# pinheader_pigoda_v2.net
KiCad netlist of a schematic drawn in EAGLE
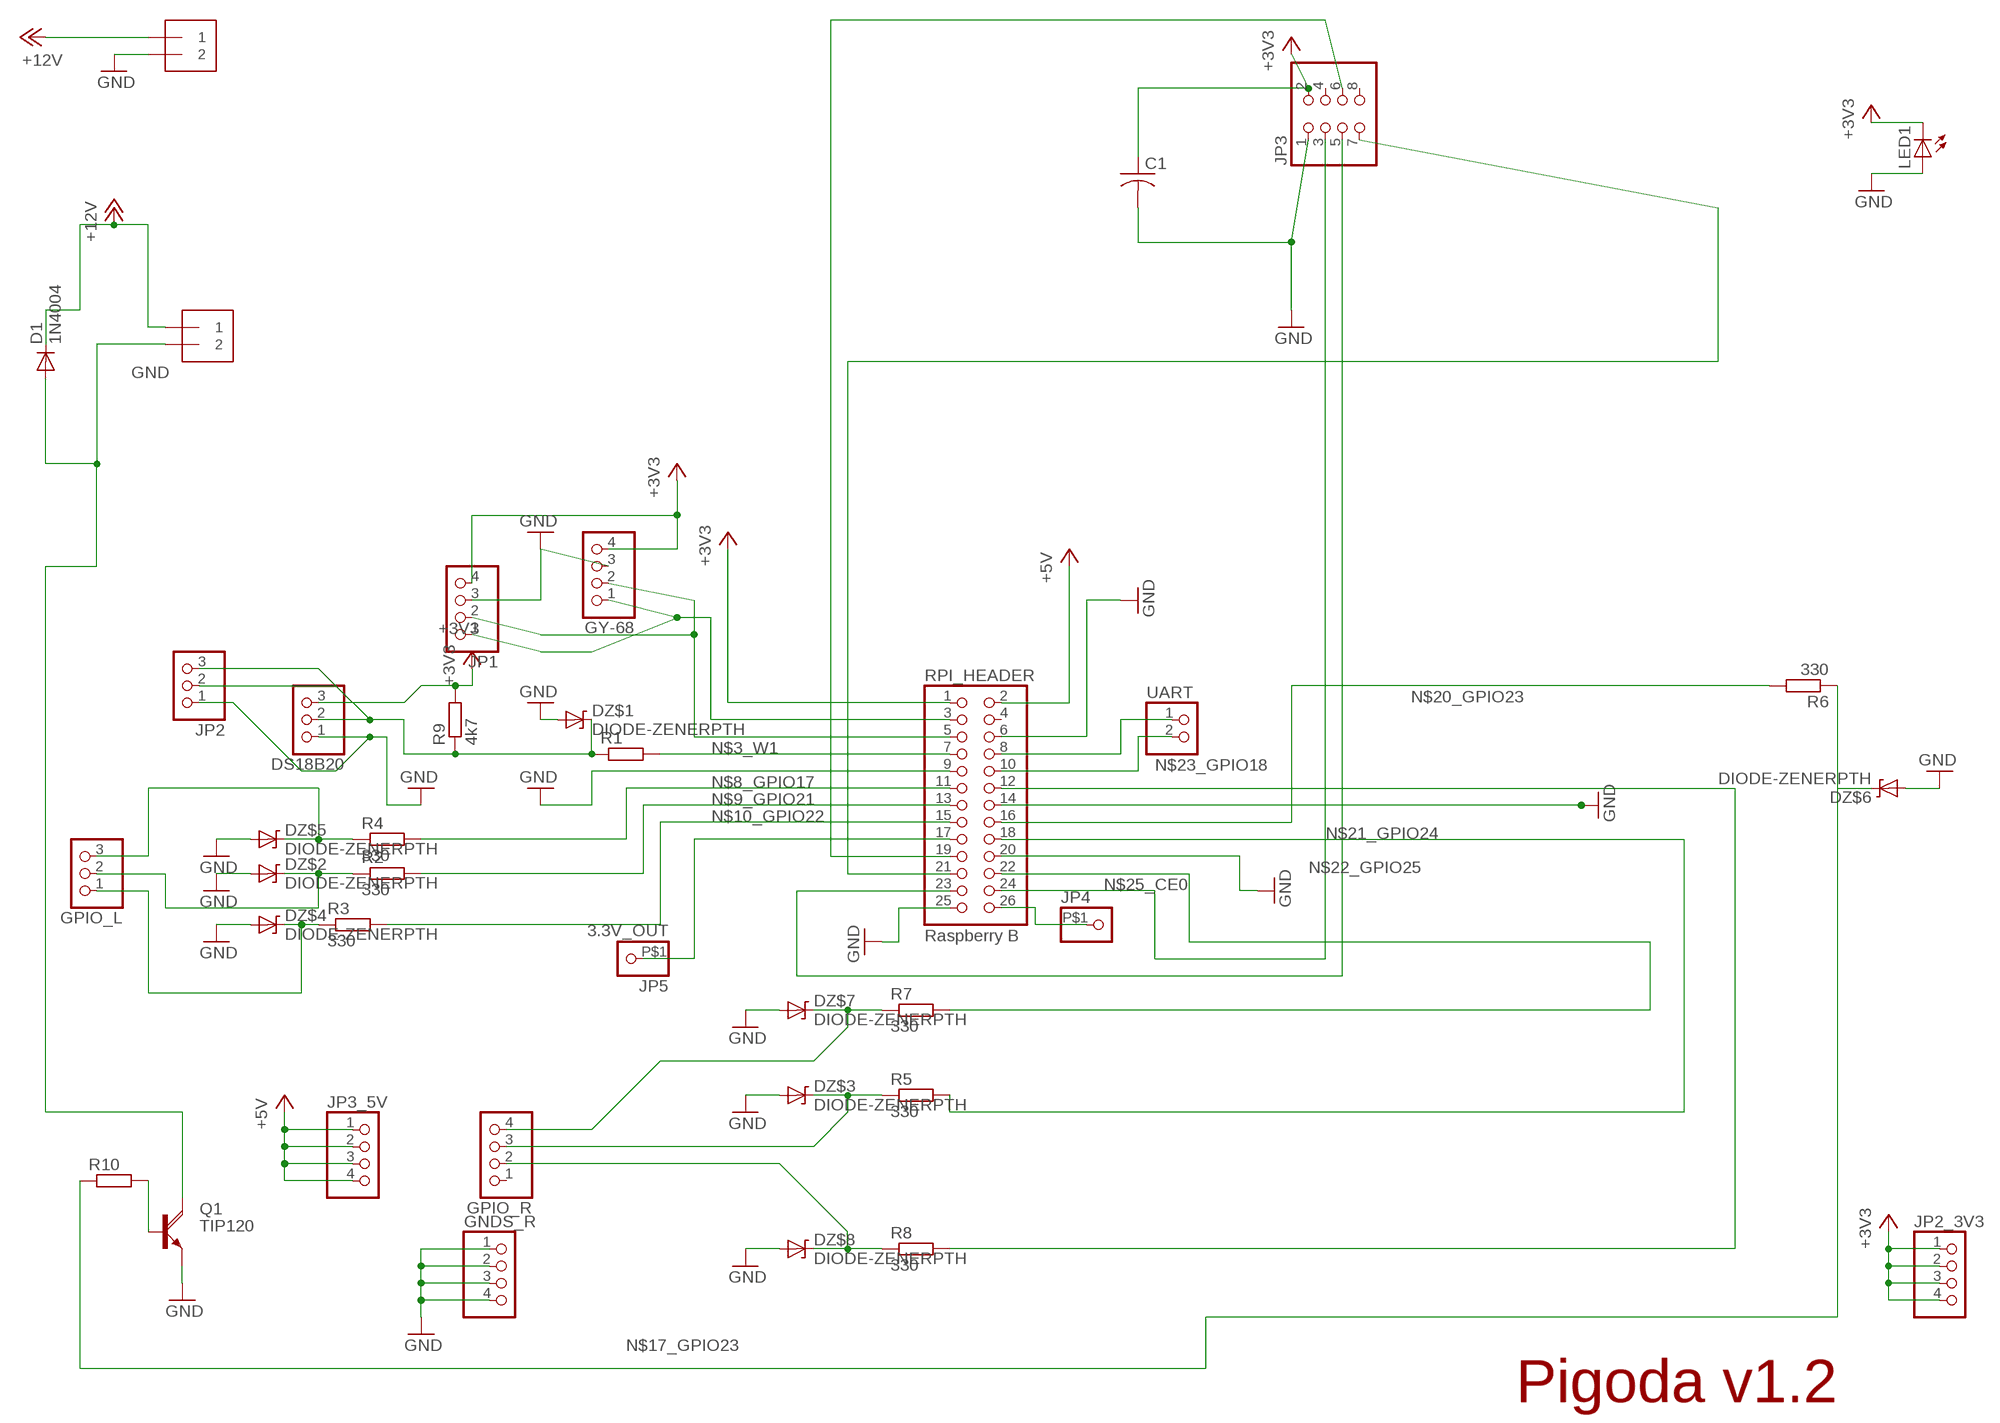
[diagram p0: schematic, sheet 1]

(export (version "E")
  (design (tool "Eeschema 10.0.6"))
  (components
    (comp (ref "C1")
      (value "C-US025-025X050")
      (footprint "eagle-import:C025-025X050")
      (libsource (lib "eagle-import") (part "C-US025-025X050"))
    )
    (comp (ref "D1")
      (value "1N4004")
      (footprint "eagle-import:DO41-10")
      (libsource (lib "eagle-import") (part "1N4004"))
    )
    (comp (ref "DS18B20")
      (value "PINHD-1X3")
      (footprint "eagle-import:1X03")
      (libsource (lib "eagle-import") (part "PINHD-1X3"))
    )
    (comp (ref "DZ$1")
      (value "DIODE-ZENERPTH")
      (footprint "eagle-import:DIODE-ZENER")
      (libsource (lib "eagle-import") (part "DIODE-ZENERPTH"))
    )
    (comp (ref "DZ$2")
      (value "DIODE-ZENERPTH")
      (footprint "eagle-import:DIODE-ZENER")
      (libsource (lib "eagle-import") (part "DIODE-ZENERPTH"))
    )
    (comp (ref "DZ$3")
      (value "DIODE-ZENERPTH")
      (footprint "eagle-import:DIODE-ZENER")
      (libsource (lib "eagle-import") (part "DIODE-ZENERPTH"))
    )
    (comp (ref "DZ$4")
      (value "DIODE-ZENERPTH")
      (footprint "eagle-import:DIODE-ZENER")
      (libsource (lib "eagle-import") (part "DIODE-ZENERPTH"))
    )
    (comp (ref "DZ$5")
      (value "DIODE-ZENERPTH")
      (footprint "eagle-import:DIODE-ZENER")
      (libsource (lib "eagle-import") (part "DIODE-ZENERPTH"))
    )
    (comp (ref "DZ$6")
      (value "DIODE-ZENERPTH")
      (footprint "eagle-import:DIODE-ZENER")
      (libsource (lib "eagle-import") (part "DIODE-ZENERPTH"))
    )
    (comp (ref "DZ$7")
      (value "DIODE-ZENERPTH")
      (footprint "eagle-import:DIODE-ZENER")
      (libsource (lib "eagle-import") (part "DIODE-ZENERPTH"))
    )
    (comp (ref "DZ$8")
      (value "DIODE-ZENERPTH")
      (footprint "eagle-import:DIODE-ZENER")
      (libsource (lib "eagle-import") (part "DIODE-ZENERPTH"))
    )
    (comp (ref "GNDS_R")
      (value "PINHD-1X4")
      (footprint "eagle-import:1X04")
      (libsource (lib "eagle-import") (part "PINHD-1X4"))
    )
    (comp (ref "GPIO_L")
      (value "PINHD-1X3")
      (footprint "eagle-import:1X03")
      (libsource (lib "eagle-import") (part "PINHD-1X3"))
    )
    (comp (ref "GPIO_R")
      (value "PINHD-1X4")
      (footprint "eagle-import:1X04")
      (libsource (lib "eagle-import") (part "PINHD-1X4"))
    )
    (comp (ref "GY-68")
      (value "PINHD-1X4")
      (footprint "eagle-import:1X04")
      (libsource (lib "eagle-import") (part "PINHD-1X4"))
    )
    (comp (ref "JP1")
      (value "PINHD-1X4")
      (footprint "eagle-import:1X04")
      (libsource (lib "eagle-import") (part "PINHD-1X4"))
    )
    (comp (ref "JP2")
      (value "PINHD-1X3")
      (footprint "eagle-import:1X03")
      (libsource (lib "eagle-import") (part "PINHD-1X3"))
    )
    (comp (ref "JP2_3V3")
      (value "PINHD-1X4")
      (footprint "eagle-import:1X04")
      (libsource (lib "eagle-import") (part "PINHD-1X4"))
    )
    (comp (ref "JP3")
      (value "PINHD-2X4/90")
      (footprint "eagle-import:2X04_90")
      (libsource (lib "eagle-import") (part "PINHD-2X4/90"))
    )
    (comp (ref "JP3_5V")
      (value "PINHD-1X4")
      (footprint "eagle-import:1X04")
      (libsource (lib "eagle-import") (part "PINHD-1X4"))
    )
    (comp (ref "JP4")
      (value "PINHD-1X1-BIGPOGO")
      (footprint "eagle-import:1X1-BIGPOGO")
      (libsource (lib "eagle-import") (part "PINHD-1X1-BIGPOGO"))
    )
    (comp (ref "JP5")
      (value "3.3V_OUT")
      (footprint "eagle-import:1X1-BIGPOGO")
      (libsource (lib "eagle-import") (part "PINHD-1X1-BIGPOGO"))
    )
    (comp (ref "LED1")
      (value "LED3MM")
      (footprint "eagle-import:LED3MM")
      (libsource (lib "eagle-import") (part "LED3MM"))
    )
    (comp (ref "Q1")
      (value "TIP120")
      (footprint "eagle-import:TO220AH")
      (libsource (lib "eagle-import") (part "TIP120"))
    )
    (comp (ref "R1")
      (value "R-EU_0204/7")
      (footprint "eagle-import:0204_7")
      (libsource (lib "eagle-import") (part "R-EU_0204/7"))
    )
    (comp (ref "R2")
      (value "330")
      (footprint "eagle-import:0204_7")
      (libsource (lib "eagle-import") (part "R-EU_0204/7"))
    )
    (comp (ref "R3")
      (value "330")
      (footprint "eagle-import:0204_7")
      (libsource (lib "eagle-import") (part "R-EU_0204/7"))
    )
    (comp (ref "R4")
      (value "330")
      (footprint "eagle-import:0204_7")
      (libsource (lib "eagle-import") (part "R-EU_0204/7"))
    )
    (comp (ref "R5")
      (value "330")
      (footprint "eagle-import:0204_7")
      (libsource (lib "eagle-import") (part "R-EU_0204/7"))
    )
    (comp (ref "R6")
      (value "330")
      (footprint "eagle-import:0204_7")
      (libsource (lib "eagle-import") (part "R-EU_0204/7"))
    )
    (comp (ref "R7")
      (value "330")
      (footprint "eagle-import:0204_7")
      (libsource (lib "eagle-import") (part "R-EU_0204/7"))
    )
    (comp (ref "R8")
      (value "330")
      (footprint "eagle-import:0204_7")
      (libsource (lib "eagle-import") (part "R-EU_0204/7"))
    )
    (comp (ref "R9")
      (value "4k7")
      (footprint "eagle-import:0204_5")
      (libsource (lib "eagle-import") (part "R-EU_0204/5"))
    )
    (comp (ref "R10")
      (value "R-EU_0204/5")
      (footprint "eagle-import:0204_5")
      (libsource (lib "eagle-import") (part "R-EU_0204/5"))
    )
    (comp (ref "RPI_HEADER")
      (value "Raspberry B")
      (footprint "eagle-import:2X13")
      (libsource (lib "eagle-import") (part "PINHD-2X13"))
    )
    (comp (ref "UART")
      (value "PINHD-1X2")
      (footprint "eagle-import:1X02")
      (libsource (lib "eagle-import") (part "PINHD-1X2"))
    )
    (comp (ref "X1_DC_OUT")
      (value "1X2-3.5MM")
      (footprint "eagle-import:1X2-3.5MM")
      (libsource (lib "eagle-import") (part "1X2-3.5MM"))
    )
    (comp (ref "X2_DC_IN")
      (value "1X2-3.5MM")
      (footprint "eagle-import:1X2-3.5MM")
      (libsource (lib "eagle-import") (part "1X2-3.5MM"))
    )
  )
  (nets
    (net (code "1") (name "+3V3") (class "Default")
      (node (ref "C1") (pin "1") (pinfunction "1_1") (pintype "passive"))
      (node (ref "DS18B20") (pin "3") (pinfunction "3_3") (pintype "passive"))
      (node (ref "GY-68") (pin "4") (pinfunction "4_4") (pintype "passive"))
      (node (ref "JP1") (pin "4") (pinfunction "4_4") (pintype "passive"))
      (node (ref "JP2") (pin "3") (pinfunction "3_3") (pintype "passive"))
      (node (ref "JP2_3V3") (pin "1") (pinfunction "1_1") (pintype "passive"))
      (node (ref "JP2_3V3") (pin "2") (pinfunction "2_2") (pintype "passive"))
      (node (ref "JP2_3V3") (pin "3") (pinfunction "3_3") (pintype "passive"))
      (node (ref "JP2_3V3") (pin "4") (pinfunction "4_4") (pintype "passive"))
      (node (ref "JP3") (pin "2") (pinfunction "2_2") (pintype "passive"))
      (node (ref "LED1") (pin "K") (pinfunction "C_K") (pintype "passive"))
      (node (ref "R9") (pin "2") (pinfunction "2_2") (pintype "passive"))
      (node (ref "RPI_HEADER") (pin "1") (pinfunction "1_1") (pintype "passive"))
    )
    (net (code "2") (name "+5V") (class "Default")
      (node (ref "JP3_5V") (pin "1") (pinfunction "1_1") (pintype "passive"))
      (node (ref "JP3_5V") (pin "2") (pinfunction "2_2") (pintype "passive"))
      (node (ref "JP3_5V") (pin "3") (pinfunction "3_3") (pintype "passive"))
      (node (ref "JP3_5V") (pin "4") (pinfunction "4_4") (pintype "passive"))
      (node (ref "RPI_HEADER") (pin "2") (pinfunction "2_2") (pintype "passive"))
    )
    (net (code "3") (name "+12V") (class "Default")
      (node (ref "D1") (pin "C") (pinfunction "C_C") (pintype "passive"))
      (node (ref "X1_DC_OUT") (pin "1") (pinfunction "1_1") (pintype "passive"))
      (node (ref "X2_DC_IN") (pin "1") (pinfunction "1_1") (pintype "passive"))
    )
    (net (code "4") (name "/N$3_W1") (class "Default")
      (node (ref "R1") (pin "2") (pinfunction "2_2") (pintype "passive"))
      (node (ref "RPI_HEADER") (pin "7") (pinfunction "7_7") (pintype "passive"))
    )
    (net (code "5") (name "/N$8_GPIO17") (class "Default")
      (node (ref "R4") (pin "2") (pinfunction "2_2") (pintype "passive"))
      (node (ref "RPI_HEADER") (pin "11") (pinfunction "11_11") (pintype "passive"))
    )
    (net (code "6") (name "/N$9_GPIO21") (class "Default")
      (node (ref "R2") (pin "2") (pinfunction "2_2") (pintype "passive"))
      (node (ref "RPI_HEADER") (pin "13") (pinfunction "13_13") (pintype "passive"))
    )
    (net (code "7") (name "/N$10_GPIO22") (class "Default")
      (node (ref "R3") (pin "2") (pinfunction "2_2") (pintype "passive"))
      (node (ref "RPI_HEADER") (pin "15") (pinfunction "15_15") (pintype "passive"))
    )
    (net (code "8") (name "/N$17_GPIO23") (class "Default")
      (node (ref "DZ$6") (pin "P$1") (pinfunction "C_P$1") (pintype "passive"))
      (node (ref "R10") (pin "1") (pinfunction "1_1") (pintype "passive"))
      (node (ref "R6") (pin "1") (pinfunction "1_1") (pintype "passive"))
    )
    (net (code "9") (name "/N$20_GPIO23") (class "Default")
      (node (ref "R6") (pin "2") (pinfunction "2_2") (pintype "passive"))
      (node (ref "RPI_HEADER") (pin "16") (pinfunction "16_16") (pintype "passive"))
    )
    (net (code "10") (name "/N$21_GPIO24") (class "Default")
      (node (ref "R5") (pin "2") (pinfunction "2_2") (pintype "passive"))
      (node (ref "RPI_HEADER") (pin "18") (pinfunction "18_18") (pintype "passive"))
    )
    (net (code "11") (name "/N$22_GPIO25") (class "Default")
      (node (ref "R7") (pin "2") (pinfunction "2_2") (pintype "passive"))
      (node (ref "RPI_HEADER") (pin "22") (pinfunction "22_22") (pintype "passive"))
    )
    (net (code "12") (name "/N$23_GPIO18") (class "Default")
      (node (ref "R8") (pin "2") (pinfunction "2_2") (pintype "passive"))
      (node (ref "RPI_HEADER") (pin "12") (pinfunction "12_12") (pintype "passive"))
    )
    (net (code "13") (name "/N$25_CE0") (class "Default")
      (node (ref "JP3") (pin "3") (pinfunction "3_3") (pintype "passive"))
      (node (ref "RPI_HEADER") (pin "24") (pinfunction "24_24") (pintype "passive"))
    )
    (net (code "14") (name "GND") (class "Default")
      (node (ref "C1") (pin "2") (pinfunction "2_2") (pintype "passive"))
      (node (ref "D1") (pin "A") (pinfunction "A_A") (pintype "passive"))
      (node (ref "DS18B20") (pin "1") (pinfunction "1_1") (pintype "passive"))
      (node (ref "DZ$1") (pin "P$2") (pinfunction "A_P$2") (pintype "passive"))
      (node (ref "DZ$2") (pin "P$2") (pinfunction "A_P$2") (pintype "passive"))
      (node (ref "DZ$3") (pin "P$2") (pinfunction "A_P$2") (pintype "passive"))
      (node (ref "DZ$4") (pin "P$2") (pinfunction "A_P$2") (pintype "passive"))
      (node (ref "DZ$5") (pin "P$2") (pinfunction "A_P$2") (pintype "passive"))
      (node (ref "DZ$6") (pin "P$2") (pinfunction "A_P$2") (pintype "passive"))
      (node (ref "DZ$7") (pin "P$2") (pinfunction "A_P$2") (pintype "passive"))
      (node (ref "DZ$8") (pin "P$2") (pinfunction "A_P$2") (pintype "passive"))
      (node (ref "GNDS_R") (pin "1") (pinfunction "1_1") (pintype "passive"))
      (node (ref "GNDS_R") (pin "2") (pinfunction "2_2") (pintype "passive"))
      (node (ref "GNDS_R") (pin "3") (pinfunction "3_3") (pintype "passive"))
      (node (ref "GNDS_R") (pin "4") (pinfunction "4_4") (pintype "passive"))
      (node (ref "GY-68") (pin "3") (pinfunction "3_3") (pintype "passive"))
      (node (ref "JP1") (pin "3") (pinfunction "3_3") (pintype "passive"))
      (node (ref "JP2") (pin "1") (pinfunction "1_1") (pintype "passive"))
      (node (ref "JP3") (pin "1") (pinfunction "1_1") (pintype "passive"))
      (node (ref "LED1") (pin "A") (pinfunction "A_A") (pintype "passive"))
      (node (ref "Q1") (pin "C") (pinfunction "C_C") (pintype "passive"))
      (node (ref "Q1") (pin "E") (pinfunction "E_E") (pintype "passive"))
      (node (ref "RPI_HEADER") (pin "14") (pinfunction "14_14") (pintype "passive"))
      (node (ref "RPI_HEADER") (pin "20") (pinfunction "20_20") (pintype "passive"))
      (node (ref "RPI_HEADER") (pin "25") (pinfunction "25_25") (pintype "passive"))
      (node (ref "RPI_HEADER") (pin "6") (pinfunction "6_6") (pintype "passive"))
      (node (ref "RPI_HEADER") (pin "9") (pinfunction "9_9") (pintype "passive"))
      (node (ref "X1_DC_OUT") (pin "2") (pinfunction "2_2") (pintype "passive"))
      (node (ref "X2_DC_IN") (pin "2") (pinfunction "2_2") (pintype "passive"))
    )
    (net (code "15") (name "Net-(DZ$1-C)") (class "Default")
      (node (ref "DS18B20") (pin "2") (pinfunction "2_2") (pintype "passive"))
      (node (ref "DZ$1") (pin "P$1") (pinfunction "C_P$1") (pintype "passive"))
      (node (ref "JP2") (pin "2") (pinfunction "2_2") (pintype "passive"))
      (node (ref "R1") (pin "1") (pinfunction "1_1") (pintype "passive"))
      (node (ref "R9") (pin "1") (pinfunction "1_1") (pintype "passive"))
    )
    (net (code "16") (name "Net-(DZ$2-C)") (class "Default")
      (node (ref "DZ$2") (pin "P$1") (pinfunction "C_P$1") (pintype "passive"))
      (node (ref "GPIO_L") (pin "2") (pinfunction "2_2") (pintype "passive"))
      (node (ref "R2") (pin "1") (pinfunction "1_1") (pintype "passive"))
    )
    (net (code "17") (name "Net-(DZ$3-C)") (class "Default")
      (node (ref "DZ$3") (pin "P$1") (pinfunction "C_P$1") (pintype "passive"))
      (node (ref "GPIO_R") (pin "3") (pinfunction "3_3") (pintype "passive"))
      (node (ref "R5") (pin "1") (pinfunction "1_1") (pintype "passive"))
    )
    (net (code "18") (name "Net-(DZ$4-C)") (class "Default")
      (node (ref "DZ$4") (pin "P$1") (pinfunction "C_P$1") (pintype "passive"))
      (node (ref "GPIO_L") (pin "1") (pinfunction "1_1") (pintype "passive"))
      (node (ref "R3") (pin "1") (pinfunction "1_1") (pintype "passive"))
    )
    (net (code "19") (name "Net-(DZ$5-C)") (class "Default")
      (node (ref "DZ$5") (pin "P$1") (pinfunction "C_P$1") (pintype "passive"))
      (node (ref "GPIO_L") (pin "3") (pinfunction "3_3") (pintype "passive"))
      (node (ref "R4") (pin "1") (pinfunction "1_1") (pintype "passive"))
    )
    (net (code "20") (name "Net-(DZ$7-C)") (class "Default")
      (node (ref "DZ$7") (pin "P$1") (pinfunction "C_P$1") (pintype "passive"))
      (node (ref "GPIO_R") (pin "4") (pinfunction "4_4") (pintype "passive"))
      (node (ref "R7") (pin "1") (pinfunction "1_1") (pintype "passive"))
    )
    (net (code "21") (name "Net-(DZ$8-C)") (class "Default")
      (node (ref "DZ$8") (pin "P$1") (pinfunction "C_P$1") (pintype "passive"))
      (node (ref "GPIO_R") (pin "2") (pinfunction "2_2") (pintype "passive"))
      (node (ref "R8") (pin "1") (pinfunction "1_1") (pintype "passive"))
    )
    (net (code "22") (name "Net-(GY-68-Pad1)") (class "Default")
      (node (ref "GY-68") (pin "1") (pinfunction "1_1") (pintype "passive"))
      (node (ref "JP1") (pin "1") (pinfunction "1_1") (pintype "passive"))
      (node (ref "RPI_HEADER") (pin "3") (pinfunction "3_3") (pintype "passive"))
    )
    (net (code "23") (name "Net-(GY-68-Pad2)") (class "Default")
      (node (ref "GY-68") (pin "2") (pinfunction "2_2") (pintype "passive"))
      (node (ref "JP1") (pin "2") (pinfunction "2_2") (pintype "passive"))
      (node (ref "RPI_HEADER") (pin "5") (pinfunction "5_5") (pintype "passive"))
    )
    (net (code "24") (name "Net-(JP3-Pad5)") (class "Default")
      (node (ref "JP3") (pin "5") (pinfunction "5_5") (pintype "passive"))
      (node (ref "RPI_HEADER") (pin "23") (pinfunction "23_23") (pintype "passive"))
    )
    (net (code "25") (name "Net-(JP3-Pad6)") (class "Default")
      (node (ref "JP3") (pin "6") (pinfunction "6_6") (pintype "passive"))
      (node (ref "RPI_HEADER") (pin "19") (pinfunction "19_19") (pintype "passive"))
    )
    (net (code "26") (name "Net-(JP3-Pad7)") (class "Default")
      (node (ref "JP3") (pin "7") (pinfunction "7_7") (pintype "passive"))
      (node (ref "RPI_HEADER") (pin "21") (pinfunction "21_21") (pintype "passive"))
    )
    (net (code "27") (name "Net-(JP4-1)") (class "Default")
      (node (ref "JP4") (pin "P$1") (pinfunction "1_P$1") (pintype "passive"))
      (node (ref "RPI_HEADER") (pin "26") (pinfunction "26_26") (pintype "passive"))
    )
    (net (code "28") (name "Net-(JP5-1)") (class "Default")
      (node (ref "JP5") (pin "P$1") (pinfunction "1_P$1") (pintype "passive"))
      (node (ref "RPI_HEADER") (pin "17") (pinfunction "17_17") (pintype "passive"))
    )
    (net (code "29") (name "Net-(Q1-PadB)") (class "Default")
      (node (ref "Q1") (pin "B") (pinfunction "B_B") (pintype "passive"))
      (node (ref "R10") (pin "2") (pinfunction "2_2") (pintype "passive"))
    )
    (net (code "30") (name "Net-(RPI_HEADER-Pad8)") (class "Default")
      (node (ref "RPI_HEADER") (pin "8") (pinfunction "8_8") (pintype "passive"))
      (node (ref "UART") (pin "1") (pinfunction "1_1") (pintype "passive"))
    )
    (net (code "31") (name "Net-(RPI_HEADER-Pad10)") (class "Default")
      (node (ref "RPI_HEADER") (pin "10") (pinfunction "10_10") (pintype "passive"))
      (node (ref "UART") (pin "2") (pinfunction "2_2") (pintype "passive"))
    )
    (net (code "32") (name "unconnected-(GPIO_R-Pad1)") (class "Default")
      (node (ref "GPIO_R") (pin "1") (pinfunction "1_1") (pintype "passive"))
    )
    (net (code "33") (name "unconnected-(JP3-Pad4)") (class "Default")
      (node (ref "JP3") (pin "4") (pinfunction "4_4") (pintype "passive"))
    )
    (net (code "34") (name "unconnected-(JP3-Pad8)") (class "Default")
      (node (ref "JP3") (pin "8") (pinfunction "8_8") (pintype "passive"))
    )
    (net (code "35") (name "unconnected-(RPI_HEADER-Pad4)") (class "Default")
      (node (ref "RPI_HEADER") (pin "4") (pinfunction "4_4") (pintype "passive"))
    )
  )
)
